# Main_Connectors.net
KiCad netlist of a schematic drawn in Altium Designer
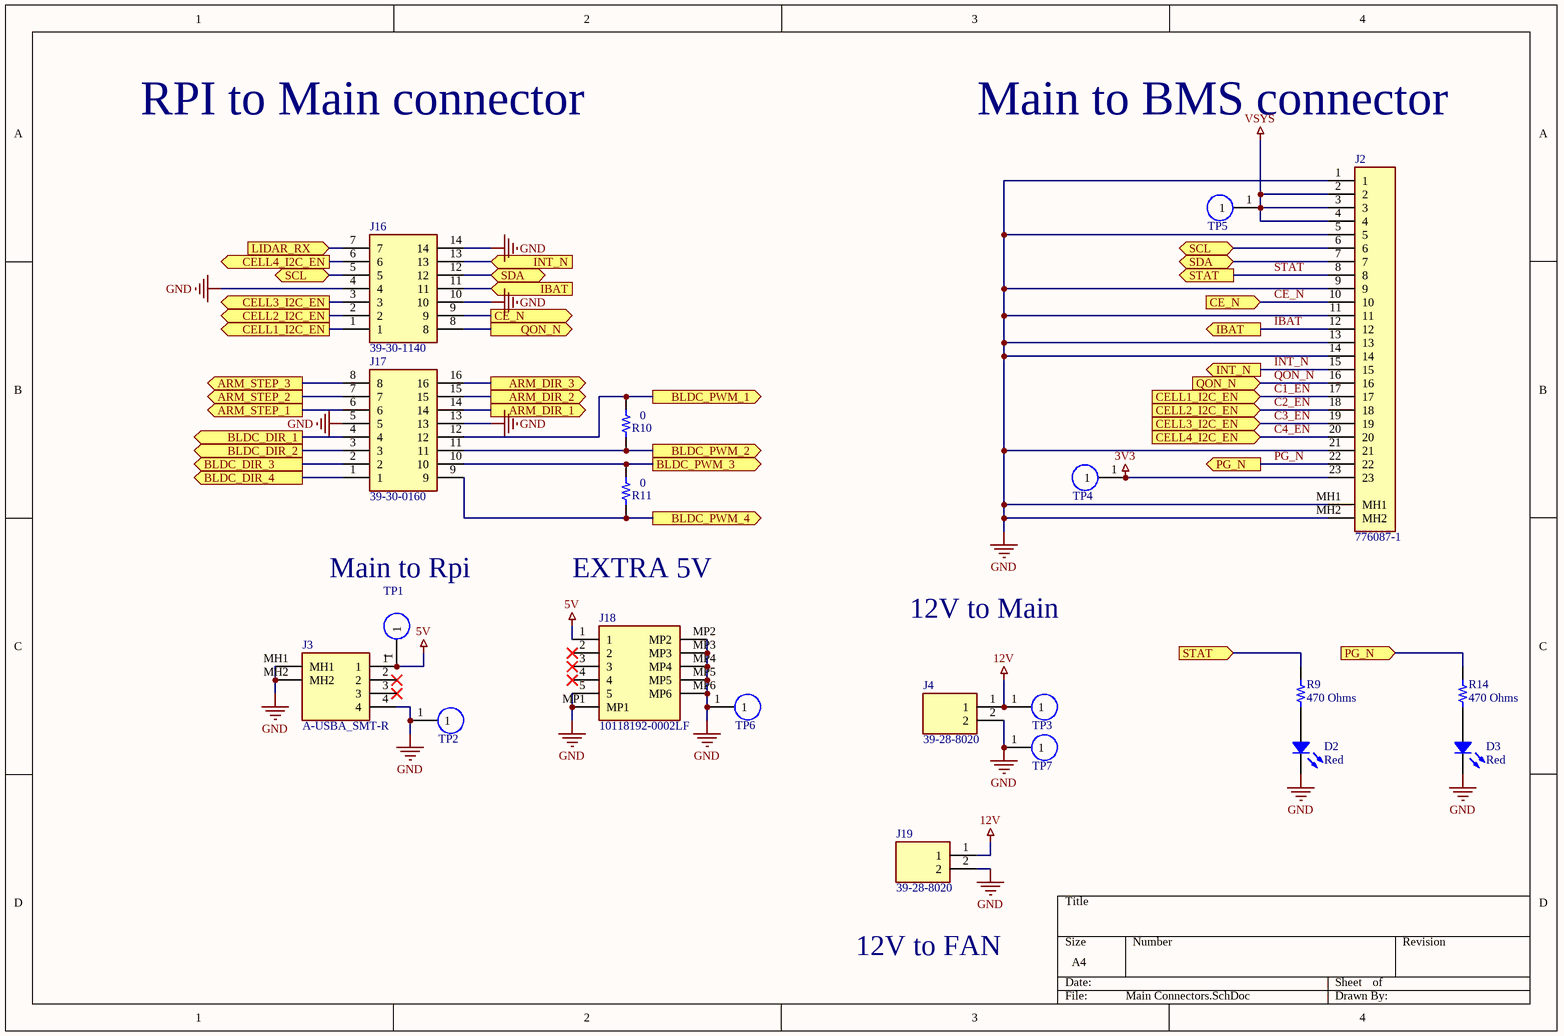
[diagram p0: Main Connectors.SchDoc]

(export (version "E")
  (design (tool "Eeschema 10.0.6"))
  (components
    (comp (ref "D2")
      (value "Red")
      (footprint "LED 0805_2012 RED")
      (description "LED RED DIFFUSED 0805 SMD")
      (fields
        (field (name "PART NUMBER") "CMD17-21VRD/TR8")
        (field (name "MANUFACTURER") "Visual Communications Company - VCC")
      )
      (libsource (lib "Celestial Altium Library - altium_library") (part "LED"))
    )
    (comp (ref "D3")
      (value "Red")
      (footprint "LED 0805_2012 RED")
      (description "LED RED DIFFUSED 0805 SMD")
      (fields
        (field (name "PART NUMBER") "CMD17-21VRD/TR8")
        (field (name "MANUFACTURER") "Visual Communications Company - VCC")
      )
      (libsource (lib "Celestial Altium Library - altium_library") (part "LED"))
    )
    (comp (ref "J2")
      (value "776087-1")
      (footprint "SamacSys:7760871")
      (description "Connector")
      (fields (field (name "MOUSER PART NUMBER") "571-776087-1"))
      (libsource (lib "SamacSys") (part "776087-1"))
    )
    (comp (ref "J3")
      (value "A-USBA_SMT-R")
      (footprint "SamacSys:AUSBASMTR")
      (description "Connector")
      (fields (field (name "MANUFACTURER_PART_NUMBER") "A-USBA/SMT-R"))
      (libsource (lib "*") (part "A-USBA_SMT-R"))
    )
    (comp (ref "J4")
      (value "39-28-8020")
      (footprint "SamacSys:SHDR2W125P550X420_2X1_540X960X1310P")
      (description "Connector")
      (fields (field (name "MOUSER PART NUMBER") "538-39-28-8020"))
      (libsource (lib "SamacSys") (part "39-28-8020"))
    )
    (comp (ref "J16")
      (value "39-30-1140")
      (footprint "SamacSys:39301142")
      (description "Connector")
      (fields (field (name "MOUSER PART NUMBER") "538-39-30-1140"))
      (libsource (lib "*") (part "39-30-1140"))
    )
    (comp (ref "J17")
      (value "39-30-0160")
      (footprint "SamacSys:39301160")
      (description "Connector")
      (fields (field (name "MOUSER PART NUMBER") "538-39-30-0160"))
      (libsource (lib "SamacSys") (part "39-30-0160"))
    )
    (comp (ref "J18")
      (value "10118192-0002LF")
      (footprint "SamacSys:101181920002LF")
      (description "Connector")
      (fields (field (name "MOUSER PART NUMBER") "649-10118192-0002LF"))
      (libsource (lib "*") (part "10118192-0002LF"))
    )
    (comp (ref "J19")
      (value "39-28-8020")
      (footprint "SamacSys:SHDR2W125P550X420_2X1_540X960X1310P")
      (description "Connector")
      (fields (field (name "MOUSER PART NUMBER") "538-39-28-8020"))
      (libsource (lib "SamacSys") (part "39-28-8020"))
    )
    (comp (ref "R9")
      (value "470 Ohms")
      (footprint "RES 0603_1608")
      (description "RES SMD 470 OHM 1% 1/10W 0603")
      (fields
        (field (name "PART NUMBER") "ERJ-3EKF4700V")
        (field (name "MANUFACTURER") "Panasonic Electronic Components")
      )
      (libsource (lib "Celestial Altium Library - altium_library") (part "Resistor"))
    )
    (comp (ref "R10")
      (value "0")
      (footprint "RES 0603_1608")
      (description "RES 0 OHM JUMPER 0603")
      (fields
        (field (name "PART NUMBER") "TLRZ1JTTD")
        (field (name "MANUFACTURER") "KOA Speer Electronics, Inc.")
      )
      (libsource (lib "Celestial Altium Library - altium_library") (part "Resistor"))
    )
    (comp (ref "R11")
      (value "0")
      (footprint "RES 0603_1608")
      (description "RES 0 OHM JUMPER 0603")
      (fields
        (field (name "PART NUMBER") "TLRZ1JTTD")
        (field (name "MANUFACTURER") "KOA Speer Electronics, Inc.")
      )
      (libsource (lib "Celestial Altium Library - altium_library") (part "Resistor"))
    )
    (comp (ref "R14")
      (value "470 Ohms")
      (footprint "RES 0603_1608")
      (description "RES SMD 470 OHM 1% 1/10W 0603")
      (fields
        (field (name "PART NUMBER") "ERJ-3EKF4700V")
        (field (name "MANUFACTURER") "Panasonic Electronic Components")
      )
      (libsource (lib "Celestial Altium Library - altium_library") (part "Resistor"))
    )
    (comp (ref "TP1")
      (value "380-10-101-00-002000")
      (footprint "SamacSys:HDRV1W51P0X254_1X1_254X254X470P")
      (description "Connector")
      (fields (field (name "MOUSER PART NUMBER") "575-3801010100002000"))
      (libsource (lib "SamacSys") (part "380-10-101-00-002000"))
    )
    (comp (ref "TP2")
      (value "380-10-101-00-002000")
      (footprint "SamacSys:HDRV1W51P0X254_1X1_254X254X470P")
      (description "Connector")
      (fields (field (name "MOUSER PART NUMBER") "575-3801010100002000"))
      (libsource (lib "SamacSys") (part "380-10-101-00-002000"))
    )
    (comp (ref "TP3")
      (value "380-10-101-00-002000")
      (footprint "SamacSys:HDRV1W51P0X254_1X1_254X254X470P")
      (description "Connector")
      (fields (field (name "MOUSER PART NUMBER") "575-3801010100002000"))
      (libsource (lib "SamacSys") (part "380-10-101-00-002000"))
    )
    (comp (ref "TP4")
      (value "380-10-101-00-002000")
      (footprint "SamacSys:HDRV1W51P0X254_1X1_254X254X470P")
      (description "Connector")
      (fields (field (name "MOUSER PART NUMBER") "575-3801010100002000"))
      (libsource (lib "SamacSys") (part "380-10-101-00-002000"))
    )
    (comp (ref "TP5")
      (value "380-10-101-00-002000")
      (footprint "SamacSys:HDRV1W51P0X254_1X1_254X254X470P")
      (description "Connector")
      (fields (field (name "MOUSER PART NUMBER") "575-3801010100002000"))
      (libsource (lib "SamacSys") (part "380-10-101-00-002000"))
    )
    (comp (ref "TP6")
      (value "380-10-101-00-002000")
      (footprint "SamacSys:HDRV1W51P0X254_1X1_254X254X470P")
      (description "Connector")
      (fields (field (name "MOUSER PART NUMBER") "575-3801010100002000"))
      (libsource (lib "SamacSys") (part "380-10-101-00-002000"))
    )
    (comp (ref "TP7")
      (value "380-10-101-00-002000")
      (footprint "SamacSys:HDRV1W51P0X254_1X1_254X254X470P")
      (description "Connector")
      (fields (field (name "MOUSER PART NUMBER") "575-3801010100002000"))
      (libsource (lib "SamacSys") (part "380-10-101-00-002000"))
    )
  )
  (nets
    (net (code "1") (name "/ARM_DIR_1") (class "Default")
      (node (ref "J17") (pin "14") (pinfunction "14_14") (pintype "passive"))
    )
    (net (code "2") (name "/ARM_DIR_2") (class "Default")
      (node (ref "J17") (pin "15") (pinfunction "15_15") (pintype "passive"))
    )
    (net (code "3") (name "/ARM_DIR_3") (class "Default")
      (node (ref "J17") (pin "16") (pinfunction "16_16") (pintype "passive"))
    )
    (net (code "4") (name "/ARM_STEP_1") (class "Default")
      (node (ref "J17") (pin "6") (pinfunction "6_6") (pintype "passive"))
    )
    (net (code "5") (name "/ARM_STEP_2") (class "Default")
      (node (ref "J17") (pin "7") (pinfunction "7_7") (pintype "passive"))
    )
    (net (code "6") (name "/ARM_STEP_3") (class "Default")
      (node (ref "J17") (pin "8") (pinfunction "8_8") (pintype "passive"))
    )
    (net (code "7") (name "/BLDC_DIR_1") (class "Default")
      (node (ref "J17") (pin "4") (pinfunction "4_4") (pintype "passive"))
    )
    (net (code "8") (name "/BLDC_DIR_2") (class "Default")
      (node (ref "J17") (pin "3") (pinfunction "3_3") (pintype "passive"))
    )
    (net (code "9") (name "/BLDC_DIR_3") (class "Default")
      (node (ref "J17") (pin "2") (pinfunction "2_2") (pintype "passive"))
    )
    (net (code "10") (name "/BLDC_DIR_4") (class "Default")
      (node (ref "J17") (pin "1") (pinfunction "1_1") (pintype "passive"))
    )
    (net (code "11") (name "/BLDC_PWM_1") (class "Default")
      (node (ref "J17") (pin "12") (pinfunction "12_12") (pintype "passive"))
      (node (ref "R10") (pin "2") (pinfunction "2_2") (pintype "passive"))
    )
    (net (code "12") (name "/BLDC_PWM_2") (class "Default")
      (node (ref "J17") (pin "11") (pinfunction "11_11") (pintype "passive"))
      (node (ref "R10") (pin "1") (pinfunction "1_1") (pintype "passive"))
    )
    (net (code "13") (name "/BLDC_PWM_3") (class "Default")
      (node (ref "J17") (pin "10") (pinfunction "10_10") (pintype "passive"))
      (node (ref "R11") (pin "2") (pinfunction "2_2") (pintype "passive"))
    )
    (net (code "14") (name "/BLDC_PWM_4") (class "Default")
      (node (ref "J17") (pin "9") (pinfunction "9_9") (pintype "passive"))
      (node (ref "R11") (pin "1") (pinfunction "1_1") (pintype "passive"))
    )
    (net (code "15") (name "/C1_EN") (class "Default")
      (node (ref "J16") (pin "1") (pinfunction "1_1") (pintype "passive"))
      (node (ref "J2") (pin "17") (pinfunction "17_17") (pintype "passive"))
    )
    (net (code "16") (name "/C2_EN") (class "Default")
      (node (ref "J16") (pin "2") (pinfunction "2_2") (pintype "passive"))
      (node (ref "J2") (pin "18") (pinfunction "18_18") (pintype "passive"))
    )
    (net (code "17") (name "/C3_EN") (class "Default")
      (node (ref "J16") (pin "3") (pinfunction "3_3") (pintype "passive"))
      (node (ref "J2") (pin "19") (pinfunction "19_19") (pintype "passive"))
    )
    (net (code "18") (name "/C4_EN") (class "Default")
      (node (ref "J16") (pin "6") (pinfunction "6_6") (pintype "passive"))
      (node (ref "J2") (pin "20") (pinfunction "20_20") (pintype "passive"))
    )
    (net (code "19") (name "/CE_N") (class "Default")
      (node (ref "J16") (pin "9") (pinfunction "9_9") (pintype "passive"))
      (node (ref "J2") (pin "10") (pinfunction "10_10") (pintype "passive"))
    )
    (net (code "20") (name "/IBAT") (class "Default")
      (node (ref "J16") (pin "11") (pinfunction "11_11") (pintype "passive"))
      (node (ref "J2") (pin "12") (pinfunction "12_12") (pintype "passive"))
    )
    (net (code "21") (name "/INT_N") (class "Default")
      (node (ref "J16") (pin "13") (pinfunction "13_13") (pintype "passive"))
      (node (ref "J2") (pin "15") (pinfunction "15_15") (pintype "passive"))
    )
    (net (code "22") (name "/LIDAR_RX") (class "Default")
      (node (ref "J16") (pin "7") (pinfunction "7_7") (pintype "passive"))
    )
    (net (code "23") (name "/PG_N") (class "Default")
      (node (ref "J2") (pin "22") (pinfunction "22_22") (pintype "passive"))
      (node (ref "R14") (pin "2") (pinfunction "2_2") (pintype "passive"))
    )
    (net (code "24") (name "/QON_N") (class "Default")
      (node (ref "J16") (pin "8") (pinfunction "8_8") (pintype "passive"))
      (node (ref "J2") (pin "16") (pinfunction "16_16") (pintype "passive"))
    )
    (net (code "25") (name "/SCL") (class "Default")
      (node (ref "J16") (pin "5") (pinfunction "5_5") (pintype "passive"))
      (node (ref "J2") (pin "6") (pinfunction "6_6") (pintype "passive"))
    )
    (net (code "26") (name "/SDA") (class "Default")
      (node (ref "J16") (pin "12") (pinfunction "12_12") (pintype "passive"))
      (node (ref "J2") (pin "7") (pinfunction "7_7") (pintype "passive"))
    )
    (net (code "27") (name "/STAT") (class "Default")
      (node (ref "J2") (pin "8") (pinfunction "8_8") (pintype "passive"))
      (node (ref "R9") (pin "2") (pinfunction "2_2") (pintype "passive"))
    )
    (net (code "28") (name "3V3") (class "Default")
      (node (ref "J2") (pin "23") (pinfunction "23_23") (pintype "passive"))
      (node (ref "TP4") (pin "1") (pinfunction "1_1") (pintype "passive"))
    )
    (net (code "29") (name "5V") (class "Default")
      (node (ref "J18") (pin "1") (pinfunction "1_1") (pintype "passive"))
      (node (ref "J3") (pin "1") (pinfunction "1_1") (pintype "passive"))
      (node (ref "TP1") (pin "1") (pinfunction "1_1") (pintype "passive"))
    )
    (net (code "30") (name "12V") (class "Default")
      (node (ref "J19") (pin "1") (pinfunction "1_1") (pintype "passive"))
      (node (ref "J4") (pin "1") (pinfunction "1_1") (pintype "passive"))
      (node (ref "TP3") (pin "1") (pinfunction "1_1") (pintype "passive"))
    )
    (net (code "31") (name "GND") (class "Default")
      (node (ref "D2") (pin "2") (pinfunction "2_2") (pintype "passive"))
      (node (ref "D3") (pin "2") (pinfunction "2_2") (pintype "passive"))
      (node (ref "J16") (pin "10") (pinfunction "10_10") (pintype "passive"))
      (node (ref "J16") (pin "14") (pinfunction "14_14") (pintype "passive"))
      (node (ref "J16") (pin "4") (pinfunction "4_4") (pintype "passive"))
      (node (ref "J17") (pin "13") (pinfunction "13_13") (pintype "passive"))
      (node (ref "J17") (pin "5") (pinfunction "5_5") (pintype "passive"))
      (node (ref "J18") (pin "5") (pinfunction "5_5") (pintype "passive"))
      (node (ref "J18") (pin "MP1") (pinfunction "MP1_MP1") (pintype "passive"))
      (node (ref "J18") (pin "MP2") (pinfunction "MP2_MP2") (pintype "passive"))
      (node (ref "J18") (pin "MP3") (pinfunction "MP3_MP3") (pintype "passive"))
      (node (ref "J18") (pin "MP4") (pinfunction "MP4_MP4") (pintype "passive"))
      (node (ref "J18") (pin "MP5") (pinfunction "MP5_MP5") (pintype "passive"))
      (node (ref "J18") (pin "MP6") (pinfunction "MP6_MP6") (pintype "passive"))
      (node (ref "J19") (pin "2") (pinfunction "2_2") (pintype "passive"))
      (node (ref "J2") (pin "1") (pinfunction "1_1") (pintype "passive"))
      (node (ref "J2") (pin "11") (pinfunction "11_11") (pintype "passive"))
      (node (ref "J2") (pin "13") (pinfunction "13_13") (pintype "passive"))
      (node (ref "J2") (pin "14") (pinfunction "14_14") (pintype "passive"))
      (node (ref "J2") (pin "21") (pinfunction "21_21") (pintype "passive"))
      (node (ref "J2") (pin "5") (pinfunction "5_5") (pintype "passive"))
      (node (ref "J2") (pin "9") (pinfunction "9_9") (pintype "passive"))
      (node (ref "J2") (pin "MH1") (pinfunction "MH1_MH1") (pintype "passive"))
      (node (ref "J2") (pin "MH2") (pinfunction "MH2_MH2") (pintype "passive"))
      (node (ref "J3") (pin "4") (pinfunction "4_4") (pintype "passive"))
      (node (ref "J3") (pin "MH1") (pinfunction "MH1_MH1") (pintype "passive"))
      (node (ref "J3") (pin "MH2") (pinfunction "MH2_MH2") (pintype "passive"))
      (node (ref "J4") (pin "2") (pinfunction "2_2") (pintype "passive"))
      (node (ref "TP2") (pin "1") (pinfunction "1_1") (pintype "passive"))
      (node (ref "TP6") (pin "1") (pinfunction "1_1") (pintype "passive"))
      (node (ref "TP7") (pin "1") (pinfunction "1_1") (pintype "passive"))
    )
    (net (code "32") (name "Net-(D2-Pad1)") (class "Default")
      (node (ref "D2") (pin "1") (pinfunction "1_1") (pintype "passive"))
      (node (ref "R9") (pin "1") (pinfunction "1_1") (pintype "passive"))
    )
    (net (code "33") (name "Net-(D3-Pad1)") (class "Default")
      (node (ref "D3") (pin "1") (pinfunction "1_1") (pintype "passive"))
      (node (ref "R14") (pin "1") (pinfunction "1_1") (pintype "passive"))
    )
    (net (code "34") (name "VSYS") (class "Default")
      (node (ref "J2") (pin "2") (pinfunction "2_2") (pintype "passive"))
      (node (ref "J2") (pin "3") (pinfunction "3_3") (pintype "passive"))
      (node (ref "J2") (pin "4") (pinfunction "4_4") (pintype "passive"))
      (node (ref "TP5") (pin "1") (pinfunction "1_1") (pintype "passive"))
    )
    (net (code "35") (name "unconnected-(J3-Pad2)") (class "Default")
      (node (ref "J3") (pin "2") (pinfunction "2_2") (pintype "passive+no_connect"))
    )
    (net (code "36") (name "unconnected-(J3-Pad3)") (class "Default")
      (node (ref "J3") (pin "3") (pinfunction "3_3") (pintype "passive+no_connect"))
    )
    (net (code "37") (name "unconnected-(J18-Pad2)") (class "Default")
      (node (ref "J18") (pin "2") (pinfunction "2_2") (pintype "passive+no_connect"))
    )
    (net (code "38") (name "unconnected-(J18-Pad3)") (class "Default")
      (node (ref "J18") (pin "3") (pinfunction "3_3") (pintype "passive+no_connect"))
    )
    (net (code "39") (name "unconnected-(J18-Pad4)") (class "Default")
      (node (ref "J18") (pin "4") (pinfunction "4_4") (pintype "passive+no_connect"))
    )
  )
)
